# LDO-Schematic.net
KiCad netlist of a schematic drawn in Altium Designer
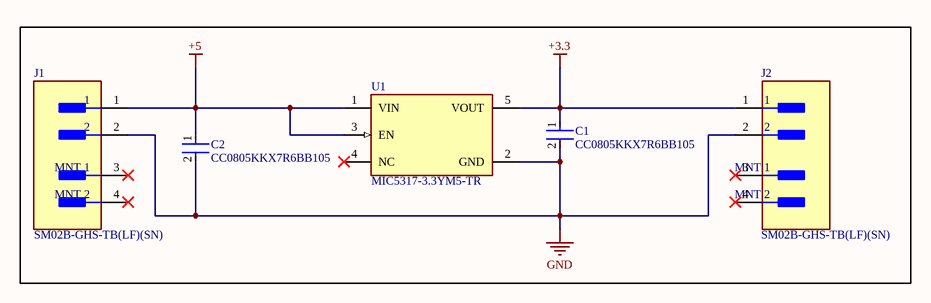
[diagram p0: LDO-Schematic.SchDoc]

(export (version "E")
  (design (tool "Eeschema 10.0.6"))
  (components
    (comp (ref "C1")
      (value "CC0805KKX7R6BB105")
      (footprint "FP-CC0805-0_85-MFG")
      (description "CAP CER 1UF 10V X7R 0805")
      (fields
        (field (name "MANUFACTURER") "Yageo")
        (field (name "OCTOPART") "https://octopart.com/cc0805kkx7r6bb105-yageo-42522859")
      )
      (libsource (lib "Altium Content Vault") (part "11868f565c42a9108669ba33697ecf6"))
    )
    (comp (ref "C2")
      (value "CC0805KKX7R6BB105")
      (footprint "FP-CC0805-0_85-MFG")
      (description "CAP CER 1UF 10V X7R 0805")
      (fields
        (field (name "MANUFACTURER") "Yageo")
        (field (name "OCTOPART") "https://octopart.com/cc0805kkx7r6bb105-yageo-42522859")
      )
      (libsource (lib "Altium Content Vault") (part "11868f565c42a9108669ba33697ecf6"))
    )
    (comp (ref "J1")
      (value "SM02B-GHS-TB(LF)(SN)")
      (footprint "FP-SM02B-GHS-TB_LF_SN-MFG")
      (description "CONN HEADER SMD R/A 2POS 1.25MM")
      (libsource (lib "") (part "56ec3178a87b3978bdc1b3682cd516a_1"))
    )
    (comp (ref "J2")
      (value "SM02B-GHS-TB(LF)(SN)")
      (footprint "FP-SM02B-GHS-TB_LF_SN-MFG")
      (description "CONN HEADER SMD R/A 2POS 1.25MM")
      (libsource (lib "Altium Content Vault") (part "56ec3178a87b3978bdc1b3682cd516a"))
    )
    (comp (ref "U1")
      (value "MIC5317-3.3YM5-TR")
      (footprint "FP-SOT23-5LD-PL-1-MFG")
      (description "IC REG LINEAR 3.3V 150MA SOT23-5")
      (libsource (lib "Altium Content Vault") (part "0a093dae7315cdc977fd108dde87457"))
    )
  )
  (nets
    (net (code "1") (name "+3.3") (class "Default")
      (node (ref "C1") (pin "1") (pinfunction "1_1") (pintype "passive"))
      (node (ref "J2") (pin "1") (pinfunction "1_1") (pintype "passive"))
      (node (ref "U1") (pin "5") (pinfunction "VOUT_5") (pintype "power_in"))
    )
    (net (code "2") (name "+5") (class "Default")
      (node (ref "C2") (pin "1") (pinfunction "1_1") (pintype "passive"))
      (node (ref "J1") (pin "1") (pinfunction "1_1") (pintype "passive"))
      (node (ref "U1") (pin "1") (pinfunction "VIN_1") (pintype "power_in"))
      (node (ref "U1") (pin "3") (pinfunction "EN_3") (pintype "input"))
    )
    (net (code "3") (name "GND") (class "Default")
      (node (ref "C1") (pin "2") (pinfunction "2_2") (pintype "passive"))
      (node (ref "C2") (pin "2") (pinfunction "2_2") (pintype "passive"))
      (node (ref "J1") (pin "2") (pinfunction "2_2") (pintype "passive"))
      (node (ref "J2") (pin "2") (pinfunction "2_2") (pintype "passive"))
      (node (ref "U1") (pin "2") (pinfunction "GND_2") (pintype "power_in"))
    )
    (net (code "4") (name "unconnected-(J1-MNT_1-Pad3)") (class "Default")
      (node (ref "J1") (pin "3") (pinfunction "MNT_1_3") (pintype "passive+no_connect"))
    )
    (net (code "5") (name "unconnected-(J1-MNT_2-Pad4)") (class "Default")
      (node (ref "J1") (pin "4") (pinfunction "MNT_2_4") (pintype "passive+no_connect"))
    )
    (net (code "6") (name "unconnected-(J2-MNT_1-Pad3)") (class "Default")
      (node (ref "J2") (pin "3") (pinfunction "MNT_1_3") (pintype "passive+no_connect"))
    )
    (net (code "7") (name "unconnected-(J2-MNT_2-Pad4)") (class "Default")
      (node (ref "J2") (pin "4") (pinfunction "MNT_2_4") (pintype "passive+no_connect"))
    )
    (net (code "8") (name "unconnected-(U1-NC-Pad4)") (class "Default")
      (node (ref "U1") (pin "4") (pinfunction "NC_4") (pintype "passive+no_connect"))
    )
  )
)
